# Base_IC.net
KiCad netlist of a schematic drawn in Altium Designer
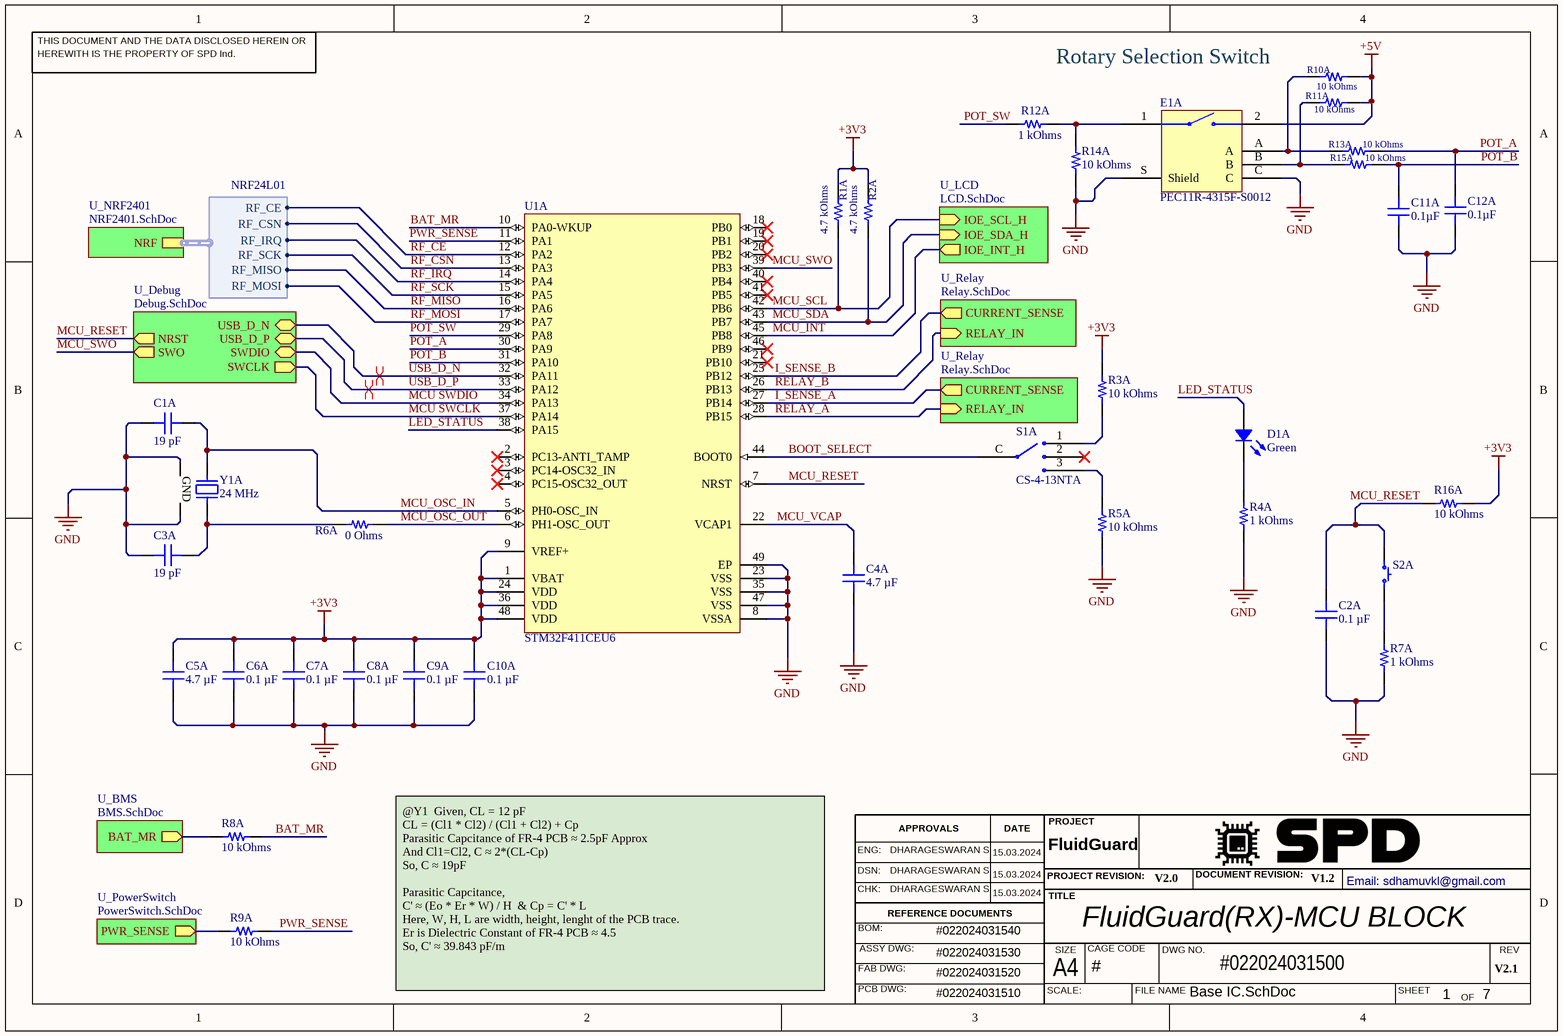
[diagram p0: Base IC.SchDoc]

(export (version "E")
  (design (tool "Eeschema 10.0.6"))
  (components
    (comp (ref "C1A")
      (value "19 pF")
      (footprint "CAP 0402_1005")
      (description "CAP CER 19PF 50VDC 0402 C0G 2%")
      (fields
        (field (name "PART NUMBER") "GJM1555C1H190GB01D")
        (field (name "MANUFACTURER") "Murata Electronics")
      )
      (libsource (lib "Postgres Altium Library - altium_library") (part "Capacitor"))
    )
    (comp (ref "C2A")
      (value "0.1 µF")
      (footprint "CAP 0402_1005")
      (description "CAP CER 100NF 10V X7R 0402")
      (fields
        (field (name "PART NUMBER") "CL05B104KP5VPNC")
        (field (name "MANUFACTURER") "Samsung Electro-Mechanics")
      )
      (libsource (lib "Postgres Altium Library - altium_library") (part "Capacitor"))
    )
    (comp (ref "C3A")
      (value "19 pF")
      (footprint "CAP 0402_1005")
      (description "CAP CER 19PF 50VDC 0402 C0G 2%")
      (fields
        (field (name "PART NUMBER") "GJM1555C1H190GB01D")
        (field (name "MANUFACTURER") "Murata Electronics")
      )
      (libsource (lib "Postgres Altium Library - altium_library") (part "Capacitor"))
    )
    (comp (ref "C4A")
      (value "4.7 µF")
      (footprint "CAP 0402_1005")
      (description "CAP0402 X5R 4.7UF 10% 10V")
      (fields
        (field (name "PART NUMBER") "GMC04X5R475K10NT")
        (field (name "MANUFACTURER") "Cal-Chip Electronics, Inc.")
      )
      (libsource (lib "Postgres Altium Library - altium_library") (part "Capacitor"))
    )
    (comp (ref "C5A")
      (value "4.7 µF")
      (footprint "CAP 0402_1005")
      (description "CAP0402 X5R 4.7UF 10% 10V")
      (fields
        (field (name "PART NUMBER") "GMC04X5R475K10NT")
        (field (name "MANUFACTURER") "Cal-Chip Electronics, Inc.")
      )
      (libsource (lib "Postgres Altium Library - altium_library") (part "Capacitor"))
    )
    (comp (ref "C6A")
      (value "0.1 µF")
      (footprint "CAP 0402_1005")
      (description "CAP CER 100NF 10V X7R 0402")
      (fields
        (field (name "PART NUMBER") "CL05B104KP5VPNC")
        (field (name "MANUFACTURER") "Samsung Electro-Mechanics")
      )
      (libsource (lib "Postgres Altium Library - altium_library") (part "Capacitor"))
    )
    (comp (ref "C7A")
      (value "0.1 µF")
      (footprint "CAP 0402_1005")
      (description "CAP CER 100NF 10V X7R 0402")
      (fields
        (field (name "PART NUMBER") "CL05B104KP5VPNC")
        (field (name "MANUFACTURER") "Samsung Electro-Mechanics")
      )
      (libsource (lib "Postgres Altium Library - altium_library") (part "Capacitor"))
    )
    (comp (ref "C8A")
      (value "0.1 µF")
      (footprint "CAP 0402_1005")
      (description "CAP CER 100NF 10V X7R 0402")
      (fields
        (field (name "PART NUMBER") "CL05B104KP5VPNC")
        (field (name "MANUFACTURER") "Samsung Electro-Mechanics")
      )
      (libsource (lib "Postgres Altium Library - altium_library") (part "Capacitor"))
    )
    (comp (ref "C9A")
      (value "0.1 µF")
      (footprint "CAP 0402_1005")
      (description "CAP CER 100NF 10V X7R 0402")
      (fields
        (field (name "PART NUMBER") "CL05B104KP5VPNC")
        (field (name "MANUFACTURER") "Samsung Electro-Mechanics")
      )
      (libsource (lib "Postgres Altium Library - altium_library") (part "Capacitor"))
    )
    (comp (ref "C10A")
      (value "0.1 µF")
      (footprint "CAP 0402_1005")
      (description "CAP CER 100NF 10V X7R 0402")
      (fields
        (field (name "PART NUMBER") "CL05B104KP5VPNC")
        (field (name "MANUFACTURER") "Samsung Electro-Mechanics")
      )
      (libsource (lib "Postgres Altium Library - altium_library") (part "Capacitor"))
    )
    (comp (ref "C11A")
      (value "0.1µF")
      (footprint "CAP 0402_1005")
      (description "CAP CER 0.1UF 10V X5R 0402")
      (fields (field (name "PART NUMBER") "LD02ZD104KAB2A") (field (name "MANUFACTURER") "AVX Corporation"))
      (libsource (lib "Postgres Altium Library - altium_library") (part "Capacitor"))
    )
    (comp (ref "C12A")
      (value "0.1µF")
      (footprint "CAP 0402_1005")
      (description "CAP CER 0.1UF 10V X5R 0402")
      (fields (field (name "PART NUMBER") "LD02ZD104KAB2A") (field (name "MANUFACTURER") "AVX Corporation"))
      (libsource (lib "Postgres Altium Library - altium_library") (part "Capacitor"))
    )
    (comp (ref "D1A")
      (value "Green")
      (footprint "LED 0402_1005 GREEN")
      (description "LED GREEN DIFFUSED 0402 SMD")
      (fields (field (name "PART NUMBER") "HSMG-C280") (field (name "MANUFACTURER") "Broadcom Limited"))
      (libsource (lib "Postgres Altium Library - altium_library") (part "LED"))
    )
    (comp (ref "E1A")
      (value "PEC11R-4315F-S0012")
      (footprint "BOURNS PEC11R-4315F-S0012")
      (description "ROTARY ENCODER MECHANICAL 12PPR")
      (fields (field (name "MANUFACTURER") "Bourns Inc."))
      (libsource (lib "Postgres Altium Library - altium_library") (part "BOURNS PEC11R-4315F-S0012"))
    )
    (comp (ref "R1A")
      (value "4.7 kOhms")
      (footprint "RES 0402_1005")
      (description "RES SMD 4.7K OHM 1% 1/16W 0402")
      (fields (field (name "PART NUMBER") "AC0402FR-074K7L") (field (name "TOLERANCE") "±1%"))
      (libsource (lib "Postgres Altium Library - altium_library") (part "Resistor"))
    )
    (comp (ref "R2A")
      (value "4.7 kOhms")
      (footprint "RES 0402_1005")
      (description "RES SMD 4.7K OHM 1% 1/16W 0402")
      (fields (field (name "PART NUMBER") "AC0402FR-074K7L") (field (name "TOLERANCE") "±1%"))
      (libsource (lib "Postgres Altium Library - altium_library") (part "Resistor"))
    )
    (comp (ref "R3A")
      (value "10 kOhms")
      (footprint "RES 0402_1005")
      (description "RES SMD 10K OHM 1% 1/16W 0402")
      (fields (field (name "PART NUMBER") "AA0402FR-0710KL") (field (name "TOLERANCE") "±1%"))
      (libsource (lib "Postgres Altium Library - altium_library") (part "Resistor"))
    )
    (comp (ref "R4A")
      (value "1 kOhms")
      (footprint "RES 0402_1005")
      (description "RES SMD 1K OHM 1% 1/16W 0402")
      (fields (field (name "PART NUMBER") "AA0402FR-071KL") (field (name "TOLERANCE") "±1%"))
      (libsource (lib "Postgres Altium Library - altium_library") (part "Resistor"))
    )
    (comp (ref "R5A")
      (value "10 kOhms")
      (footprint "RES 0402_1005")
      (description "RES SMD 10K OHM 1% 1/16W 0402")
      (fields (field (name "PART NUMBER") "AA0402FR-0710KL") (field (name "TOLERANCE") "±1%"))
      (libsource (lib "Postgres Altium Library - altium_library") (part "Resistor"))
    )
    (comp (ref "R6A")
      (value "0 Ohms")
      (footprint "RES 0402_1005")
      (description "RES SMD 0 OHM JUMPER 1/16W 0402")
      (fields (field (name "PART NUMBER") "AC0402JR-070RL") (field (name "TOLERANCE") "Jumper"))
      (libsource (lib "Postgres Altium Library - altium_library") (part "Resistor"))
    )
    (comp (ref "R7A")
      (value "1 kOhms")
      (footprint "RES 0402_1005")
      (description "RES SMD 1K OHM 1% 1/16W 0402")
      (fields (field (name "PART NUMBER") "AA0402FR-071KL") (field (name "TOLERANCE") "±1%"))
      (libsource (lib "Postgres Altium Library - altium_library") (part "Resistor"))
    )
    (comp (ref "R8A")
      (value "10 kOhms")
      (footprint "RES 0402_1005")
      (description "RES SMD 10K OHM 1% 1/16W 0402")
      (fields (field (name "PART NUMBER") "AA0402FR-0710KL") (field (name "TOLERANCE") "±1%"))
      (libsource (lib "Postgres Altium Library - altium_library") (part "Resistor"))
    )
    (comp (ref "R9A")
      (value "10 kOhms")
      (footprint "RES 0402_1005")
      (description "RES SMD 10K OHM 1% 1/16W 0402")
      (fields (field (name "PART NUMBER") "AA0402FR-0710KL") (field (name "TOLERANCE") "±1%"))
      (libsource (lib "Postgres Altium Library - altium_library") (part "Resistor"))
    )
    (comp (ref "R10A")
      (value "10 kOhms")
      (footprint "RES 0402_1005")
      (description "RES SMD 10K OHM 1% 1/16W 0402")
      (fields (field (name "PART NUMBER") "AA0402FR-0710KL") (field (name "TOLERANCE") "±1%"))
      (libsource (lib "Postgres Altium Library - altium_library") (part "Resistor"))
    )
    (comp (ref "R11A")
      (value "10 kOhms")
      (footprint "RES 0402_1005")
      (description "RES SMD 10K OHM 1% 1/16W 0402")
      (fields (field (name "PART NUMBER") "AA0402FR-0710KL") (field (name "TOLERANCE") "±1%"))
      (libsource (lib "Postgres Altium Library - altium_library") (part "Resistor"))
    )
    (comp (ref "R12A")
      (value "1 kOhms")
      (footprint "RES 0402_1005")
      (description "RES SMD 1K OHM 1% 1/16W 0402")
      (fields (field (name "PART NUMBER") "AA0402FR-071KL") (field (name "TOLERANCE") "±1%"))
      (libsource (lib "Postgres Altium Library - altium_library") (part "Resistor"))
    )
    (comp (ref "R13A")
      (value "10 kOhms")
      (footprint "RES 0402_1005")
      (description "RES SMD 10K OHM 1% 1/16W 0402")
      (fields (field (name "PART NUMBER") "AA0402FR-0710KL") (field (name "TOLERANCE") "±1%"))
      (libsource (lib "Postgres Altium Library - altium_library") (part "Resistor"))
    )
    (comp (ref "R14A")
      (value "10 kOhms")
      (footprint "RES 0402_1005")
      (description "RES SMD 10K OHM 1% 1/16W 0402")
      (fields (field (name "PART NUMBER") "AA0402FR-0710KL") (field (name "TOLERANCE") "±1%"))
      (libsource (lib "Postgres Altium Library - altium_library") (part "Resistor"))
    )
    (comp (ref "R15A")
      (value "10 kOhms")
      (footprint "RES 0402_1005")
      (description "RES SMD 10K OHM 1% 1/16W 0402")
      (fields (field (name "PART NUMBER") "AA0402FR-0710KL") (field (name "TOLERANCE") "±1%"))
      (libsource (lib "Postgres Altium Library - altium_library") (part "Resistor"))
    )
    (comp (ref "R16A")
      (value "10 kOhms")
      (footprint "RES 0402_1005")
      (description "RES SMD 10K OHM 1% 1/16W 0402")
      (fields (field (name "PART NUMBER") "AA0402FR-0710KL") (field (name "TOLERANCE") "±1%"))
      (libsource (lib "Postgres Altium Library - altium_library") (part "Resistor"))
    )
    (comp (ref "S1A")
      (value "CS-4-13NTA")
      (footprint "NIDEC COPAL CS-4-13NTA")
      (description "SWITCH ROTARY DIP SP3T 100MA 16V")
      (fields (field (name "MANUFACTURER") "Nidec Copal Electronics"))
      (libsource (lib "Postgres Altium Library - altium_library") (part "NIDEC COPAL CS-4-13NTA"))
    )
    (comp (ref "S2A")
      (value "EVP-AWED4A")
      (footprint "PANASONIC EVPAW")
      (description "3.0MM X 2.0MM / 3.3N / 0.15MM ST")
      (fields (field (name "MANUFACTURER") "Panasonic Electronic Components"))
      (libsource (lib "Postgres Altium Library - altium_library") (part "SPST-NO 2 PIN"))
    )
    (comp (ref "U1A")
      (value "STM32F411CEU6")
      (footprint "STM-UFQFPN48_L")
      (libsource (lib "Altium Content Vault") (part "MC-ARM-STM32F411-UFQFPN48"))
    )
    (comp (ref "Y1A")
      (value "24 MHz")
      (footprint "EPSON TSX-3225")
      (description "CRYSTAL 24.0000MHZ 9PF SMD")
      (fields (field (name "PART NUMBER") "TSX-3225 24.0000MF15X-AC3") (field (name "MANUFACTURER") "EPSON"))
      (libsource (lib "Postgres Altium Library - altium_library") (part "Epson Crystal TSX-3225"))
    )
  )
  (nets
    (net (code "2") (name "+3V3") (class "Default")
      (node (ref "C10A") (pin "2") (pinfunction "2_2") (pintype "passive"))
      (node (ref "C5A") (pin "2") (pinfunction "2_2") (pintype "passive"))
      (node (ref "C6A") (pin "2") (pinfunction "2_2") (pintype "passive"))
      (node (ref "C7A") (pin "2") (pinfunction "2_2") (pintype "passive"))
      (node (ref "C8A") (pin "2") (pinfunction "2_2") (pintype "passive"))
      (node (ref "C9A") (pin "2") (pinfunction "2_2") (pintype "passive"))
      (node (ref "R16A") (pin "1") (pinfunction "1_1") (pintype "passive"))
      (node (ref "R1A") (pin "2") (pinfunction "2_2") (pintype "passive"))
      (node (ref "R2A") (pin "2") (pinfunction "2_2") (pintype "passive"))
      (node (ref "R3A") (pin "2") (pinfunction "2_2") (pintype "passive"))
      (node (ref "U1A") (pin "1") (pinfunction "VBAT_1") (pintype "power_in"))
      (node (ref "U1A") (pin "24") (pinfunction "VDD_24") (pintype "power_in"))
      (node (ref "U1A") (pin "36") (pinfunction "VDD_36") (pintype "power_in"))
      (node (ref "U1A") (pin "48") (pinfunction "VDD_48") (pintype "power_in"))
      (node (ref "U1A") (pin "9") (pinfunction "VREF+_9") (pintype "power_in"))
    )
    (net (code "3") (name "+5V") (class "Default")
      (node (ref "E1A") (pin "2") (pinfunction "2_2") (pintype "passive"))
      (node (ref "R10A") (pin "2") (pinfunction "2_2") (pintype "passive"))
      (node (ref "R11A") (pin "2") (pinfunction "2_2") (pintype "passive"))
    )
    (net (code "4") (name "/BAT_MR") (class "Default")
      (node (ref "R8A") (pin "1") (pinfunction "1_1") (pintype "passive"))
      (node (ref "U1A") (pin "10") (pinfunction "PA0-WKUP_10") (pintype "bidirectional"))
    )
    (net (code "5") (name "/BAT_MR_1") (class "Default")
      (node (ref "R8A") (pin "2") (pinfunction "2_2") (pintype "passive"))
    )
    (net (code "6") (name "/BOOT_SELECT") (class "Default")
      (node (ref "S1A") (pin "C") (pinfunction "C_C") (pintype "passive"))
      (node (ref "U1A") (pin "44") (pinfunction "BOOT0_44") (pintype "input"))
    )
    (net (code "7") (name "/I_SENSE_A") (class "Default")
      (node (ref "U1A") (pin "27") (pinfunction "PB14_27") (pintype "bidirectional"))
    )
    (net (code "8") (name "/I_SENSE_B") (class "Default")
      (node (ref "U1A") (pin "25") (pinfunction "PB12_25") (pintype "bidirectional"))
    )
    (net (code "9") (name "/LED_STATUS") (class "Default")
      (node (ref "D1A") (pin "1") (pinfunction "1_1") (pintype "passive"))
      (node (ref "U1A") (pin "38") (pinfunction "PA15_38") (pintype "bidirectional"))
    )
    (net (code "10") (name "/MCU SWCLK") (class "Default")
      (node (ref "U1A") (pin "37") (pinfunction "PA14_37") (pintype "bidirectional"))
    )
    (net (code "11") (name "/MCU SWDIO") (class "Default")
      (node (ref "U1A") (pin "34") (pinfunction "PA13_34") (pintype "bidirectional"))
    )
    (net (code "12") (name "/MCU_INT") (class "Default")
      (node (ref "U1A") (pin "45") (pinfunction "PB8_45") (pintype "bidirectional"))
    )
    (net (code "13") (name "/MCU_OSC_IN") (class "Default")
      (node (ref "C1A") (pin "2") (pinfunction "2_2") (pintype "passive"))
      (node (ref "U1A") (pin "5") (pinfunction "PH0-OSC_IN_5") (pintype "bidirectional"))
      (node (ref "Y1A") (pin "1") (pinfunction "1_1") (pintype "passive"))
    )
    (net (code "14") (name "/MCU_OSC_OUT") (class "Default")
      (node (ref "R6A") (pin "2") (pinfunction "2_2") (pintype "passive"))
      (node (ref "U1A") (pin "6") (pinfunction "PH1-OSC_OUT_6") (pintype "bidirectional"))
    )
    (net (code "15") (name "/MCU_RESET") (class "Default")
      (node (ref "C2A") (pin "2") (pinfunction "2_2") (pintype "passive"))
      (node (ref "R16A") (pin "2") (pinfunction "2_2") (pintype "passive"))
      (node (ref "S2A") (pin "1") (pinfunction "1_1") (pintype "passive"))
      (node (ref "U1A") (pin "7") (pinfunction "NRST_7") (pintype "bidirectional"))
    )
    (net (code "16") (name "/MCU_SCL") (class "Default")
      (node (ref "R1A") (pin "1") (pinfunction "1_1") (pintype "passive"))
      (node (ref "U1A") (pin "42") (pinfunction "PB6_42") (pintype "bidirectional"))
    )
    (net (code "17") (name "/MCU_SDA") (class "Default")
      (node (ref "R2A") (pin "1") (pinfunction "1_1") (pintype "passive"))
      (node (ref "U1A") (pin "43") (pinfunction "PB7_43") (pintype "bidirectional"))
    )
    (net (code "18") (name "/MCU_SWO") (class "Default")
      (node (ref "U1A") (pin "39") (pinfunction "PB3_39") (pintype "bidirectional"))
    )
    (net (code "19") (name "/MCU_VCAP") (class "Default")
      (node (ref "C4A") (pin "2") (pinfunction "2_2") (pintype "passive"))
      (node (ref "U1A") (pin "22") (pinfunction "VCAP1_22") (pintype "passive"))
    )
    (net (code "20") (name "/POT_A") (class "Default")
      (node (ref "C12A") (pin "2") (pinfunction "2_2") (pintype "passive"))
      (node (ref "R13A") (pin "1") (pinfunction "1_1") (pintype "passive"))
      (node (ref "U1A") (pin "30") (pinfunction "PA9_30") (pintype "bidirectional"))
    )
    (net (code "21") (name "/POT_B") (class "Default")
      (node (ref "C11A") (pin "2") (pinfunction "2_2") (pintype "passive"))
      (node (ref "R15A") (pin "1") (pinfunction "1_1") (pintype "passive"))
      (node (ref "U1A") (pin "31") (pinfunction "PA10_31") (pintype "bidirectional"))
    )
    (net (code "22") (name "/POT_SW") (class "Default")
      (node (ref "R12A") (pin "2") (pinfunction "2_2") (pintype "passive"))
      (node (ref "U1A") (pin "29") (pinfunction "PA8_29") (pintype "bidirectional"))
    )
    (net (code "23") (name "/PWR_SENSE") (class "Default")
      (node (ref "R9A") (pin "1") (pinfunction "1_1") (pintype "passive"))
      (node (ref "U1A") (pin "11") (pinfunction "PA1_11") (pintype "bidirectional"))
    )
    (net (code "24") (name "/PWR_SENSE_1") (class "Default")
      (node (ref "R9A") (pin "2") (pinfunction "2_2") (pintype "passive"))
    )
    (net (code "25") (name "/RELAY_A") (class "Default")
      (node (ref "U1A") (pin "28") (pinfunction "PB15_28") (pintype "bidirectional"))
    )
    (net (code "26") (name "/RELAY_B") (class "Default")
      (node (ref "U1A") (pin "26") (pinfunction "PB13_26") (pintype "bidirectional"))
    )
    (net (code "27") (name "/RF_CE") (class "Default")
      (node (ref "U1A") (pin "12") (pinfunction "PA2_12") (pintype "bidirectional"))
    )
    (net (code "28") (name "/RF_CSN") (class "Default")
      (node (ref "U1A") (pin "13") (pinfunction "PA3_13") (pintype "bidirectional"))
    )
    (net (code "29") (name "/RF_IRQ") (class "Default")
      (node (ref "U1A") (pin "14") (pinfunction "PA4_14") (pintype "bidirectional"))
    )
    (net (code "30") (name "/RF_MISO") (class "Default")
      (node (ref "U1A") (pin "16") (pinfunction "PA6_16") (pintype "bidirectional"))
    )
    (net (code "31") (name "/RF_MOSI") (class "Default")
      (node (ref "U1A") (pin "17") (pinfunction "PA7_17") (pintype "bidirectional"))
    )
    (net (code "32") (name "/RF_SCK") (class "Default")
      (node (ref "U1A") (pin "15") (pinfunction "PA5_15") (pintype "bidirectional"))
    )
    (net (code "33") (name "/USB_D_N") (class "Default")
      (node (ref "U1A") (pin "32") (pinfunction "PA11_32") (pintype "bidirectional"))
    )
    (net (code "34") (name "/USB_D_P") (class "Default")
      (node (ref "U1A") (pin "33") (pinfunction "PA12_33") (pintype "bidirectional"))
    )
    (net (code "36") (name "GND") (class "Default")
      (node (ref "C10A") (pin "1") (pinfunction "1_1") (pintype "passive"))
      (node (ref "C11A") (pin "1") (pinfunction "1_1") (pintype "passive"))
      (node (ref "C12A") (pin "1") (pinfunction "1_1") (pintype "passive"))
      (node (ref "C1A") (pin "1") (pinfunction "1_1") (pintype "passive"))
      (node (ref "C2A") (pin "1") (pinfunction "1_1") (pintype "passive"))
      (node (ref "C3A") (pin "1") (pinfunction "1_1") (pintype "passive"))
      (node (ref "C4A") (pin "1") (pinfunction "1_1") (pintype "passive"))
      (node (ref "C5A") (pin "1") (pinfunction "1_1") (pintype "passive"))
      (node (ref "C6A") (pin "1") (pinfunction "1_1") (pintype "passive"))
      (node (ref "C7A") (pin "1") (pinfunction "1_1") (pintype "passive"))
      (node (ref "C8A") (pin "1") (pinfunction "1_1") (pintype "passive"))
      (node (ref "C9A") (pin "1") (pinfunction "1_1") (pintype "passive"))
      (node (ref "E1A") (pin "C") (pinfunction "C_C") (pintype "passive"))
      (node (ref "E1A") (pin "S") (pinfunction "Shield_S") (pintype "passive"))
      (node (ref "R14A") (pin "1") (pinfunction "1_1") (pintype "passive"))
      (node (ref "R4A") (pin "1") (pinfunction "1_1") (pintype "passive"))
      (node (ref "R5A") (pin "1") (pinfunction "1_1") (pintype "passive"))
      (node (ref "R7A") (pin "1") (pinfunction "1_1") (pintype "passive"))
      (node (ref "U1A") (pin "23") (pinfunction "VSS_23") (pintype "power_in"))
      (node (ref "U1A") (pin "35") (pinfunction "VSS_35") (pintype "power_in"))
      (node (ref "U1A") (pin "47") (pinfunction "VSS_47") (pintype "power_in"))
      (node (ref "U1A") (pin "49") (pinfunction "EP_49") (pintype "power_in"))
      (node (ref "U1A") (pin "8") (pinfunction "VSSA_8") (pintype "power_in"))
      (node (ref "Y1A") (pin "2") (pinfunction "GND_2") (pintype "passive"))
      (node (ref "Y1A") (pin "4") (pinfunction "GND_4") (pintype "passive"))
    )
    (net (code "37") (name "Net-(C3A-Pad2)") (class "Default")
      (node (ref "C3A") (pin "2") (pinfunction "2_2") (pintype "passive"))
      (node (ref "R6A") (pin "1") (pinfunction "1_1") (pintype "passive"))
      (node (ref "Y1A") (pin "3") (pinfunction "3_3") (pintype "passive"))
    )
    (net (code "38") (name "Net-(D1A-Pad2)") (class "Default")
      (node (ref "D1A") (pin "2") (pinfunction "2_2") (pintype "passive"))
      (node (ref "R4A") (pin "2") (pinfunction "2_2") (pintype "passive"))
    )
    (net (code "39") (name "Net-(E1A-Pad1)") (class "Default")
      (node (ref "E1A") (pin "1") (pinfunction "1_1") (pintype "passive"))
      (node (ref "R12A") (pin "1") (pinfunction "1_1") (pintype "passive"))
      (node (ref "R14A") (pin "2") (pinfunction "2_2") (pintype "passive"))
    )
    (net (code "40") (name "Net-(E1A-PadA)") (class "Default")
      (node (ref "E1A") (pin "A") (pinfunction "A_A") (pintype "passive"))
      (node (ref "R10A") (pin "1") (pinfunction "1_1") (pintype "passive"))
      (node (ref "R13A") (pin "2") (pinfunction "2_2") (pintype "passive"))
    )
    (net (code "41") (name "Net-(E1A-PadB)") (class "Default")
      (node (ref "E1A") (pin "B") (pinfunction "B_B") (pintype "passive"))
      (node (ref "R11A") (pin "1") (pinfunction "1_1") (pintype "passive"))
      (node (ref "R15A") (pin "2") (pinfunction "2_2") (pintype "passive"))
    )
    (net (code "42") (name "Net-(R3A-Pad1)") (class "Default")
      (node (ref "R3A") (pin "1") (pinfunction "1_1") (pintype "passive"))
      (node (ref "S1A") (pin "1") (pinfunction "1_1") (pintype "passive"))
    )
    (net (code "43") (name "Net-(R5A-Pad2)") (class "Default")
      (node (ref "R5A") (pin "2") (pinfunction "2_2") (pintype "passive"))
      (node (ref "S1A") (pin "3") (pinfunction "3_3") (pintype "passive"))
    )
    (net (code "44") (name "Net-(R7A-Pad2)") (class "Default")
      (node (ref "R7A") (pin "2") (pinfunction "2_2") (pintype "passive"))
      (node (ref "S2A") (pin "2") (pinfunction "2_2") (pintype "passive"))
    )
    (net (code "45") (name "unconnected-(S1A-Pad2)") (class "Default")
      (node (ref "S1A") (pin "2") (pinfunction "2_2") (pintype "passive+no_connect"))
    )
    (net (code "46") (name "unconnected-(U1A-PB0-Pad18)") (class "Default")
      (node (ref "U1A") (pin "18") (pinfunction "PB0_18") (pintype "bidirectional+no_connect"))
    )
    (net (code "47") (name "unconnected-(U1A-PB1-Pad19)") (class "Default")
      (node (ref "U1A") (pin "19") (pinfunction "PB1_19") (pintype "bidirectional+no_connect"))
    )
    (net (code "48") (name "unconnected-(U1A-PB2-Pad20)") (class "Default")
      (node (ref "U1A") (pin "20") (pinfunction "PB2_20") (pintype "bidirectional+no_connect"))
    )
    (net (code "49") (name "unconnected-(U1A-PB4-Pad40)") (class "Default")
      (node (ref "U1A") (pin "40") (pinfunction "PB4_40") (pintype "bidirectional+no_connect"))
    )
    (net (code "50") (name "unconnected-(U1A-PB5-Pad41)") (class "Default")
      (node (ref "U1A") (pin "41") (pinfunction "PB5_41") (pintype "bidirectional+no_connect"))
    )
    (net (code "51") (name "unconnected-(U1A-PB9-Pad46)") (class "Default")
      (node (ref "U1A") (pin "46") (pinfunction "PB9_46") (pintype "bidirectional+no_connect"))
    )
    (net (code "52") (name "unconnected-(U1A-PB10-Pad21)") (class "Default")
      (node (ref "U1A") (pin "21") (pinfunction "PB10_21") (pintype "bidirectional+no_connect"))
    )
    (net (code "53") (name "unconnected-(U1A-PC13-ANTI_TAMP-Pad2)") (class "Default")
      (node (ref "U1A") (pin "2") (pinfunction "PC13-ANTI_TAMP_2") (pintype "bidirectional+no_connect"))
    )
    (net (code "54") (name "unconnected-(U1A-PC14-OSC32_IN-Pad3)") (class "Default")
      (node (ref "U1A") (pin "3") (pinfunction "PC14-OSC32_IN_3") (pintype "bidirectional+no_connect"))
    )
    (net (code "55") (name "unconnected-(U1A-PC15-OSC32_OUT-Pad4)") (class "Default")
      (node (ref "U1A") (pin "4") (pinfunction "PC15-OSC32_OUT_4") (pintype "bidirectional+no_connect"))
    )
  )
)
